# Power.net
KiCad netlist of a schematic drawn in EAGLE
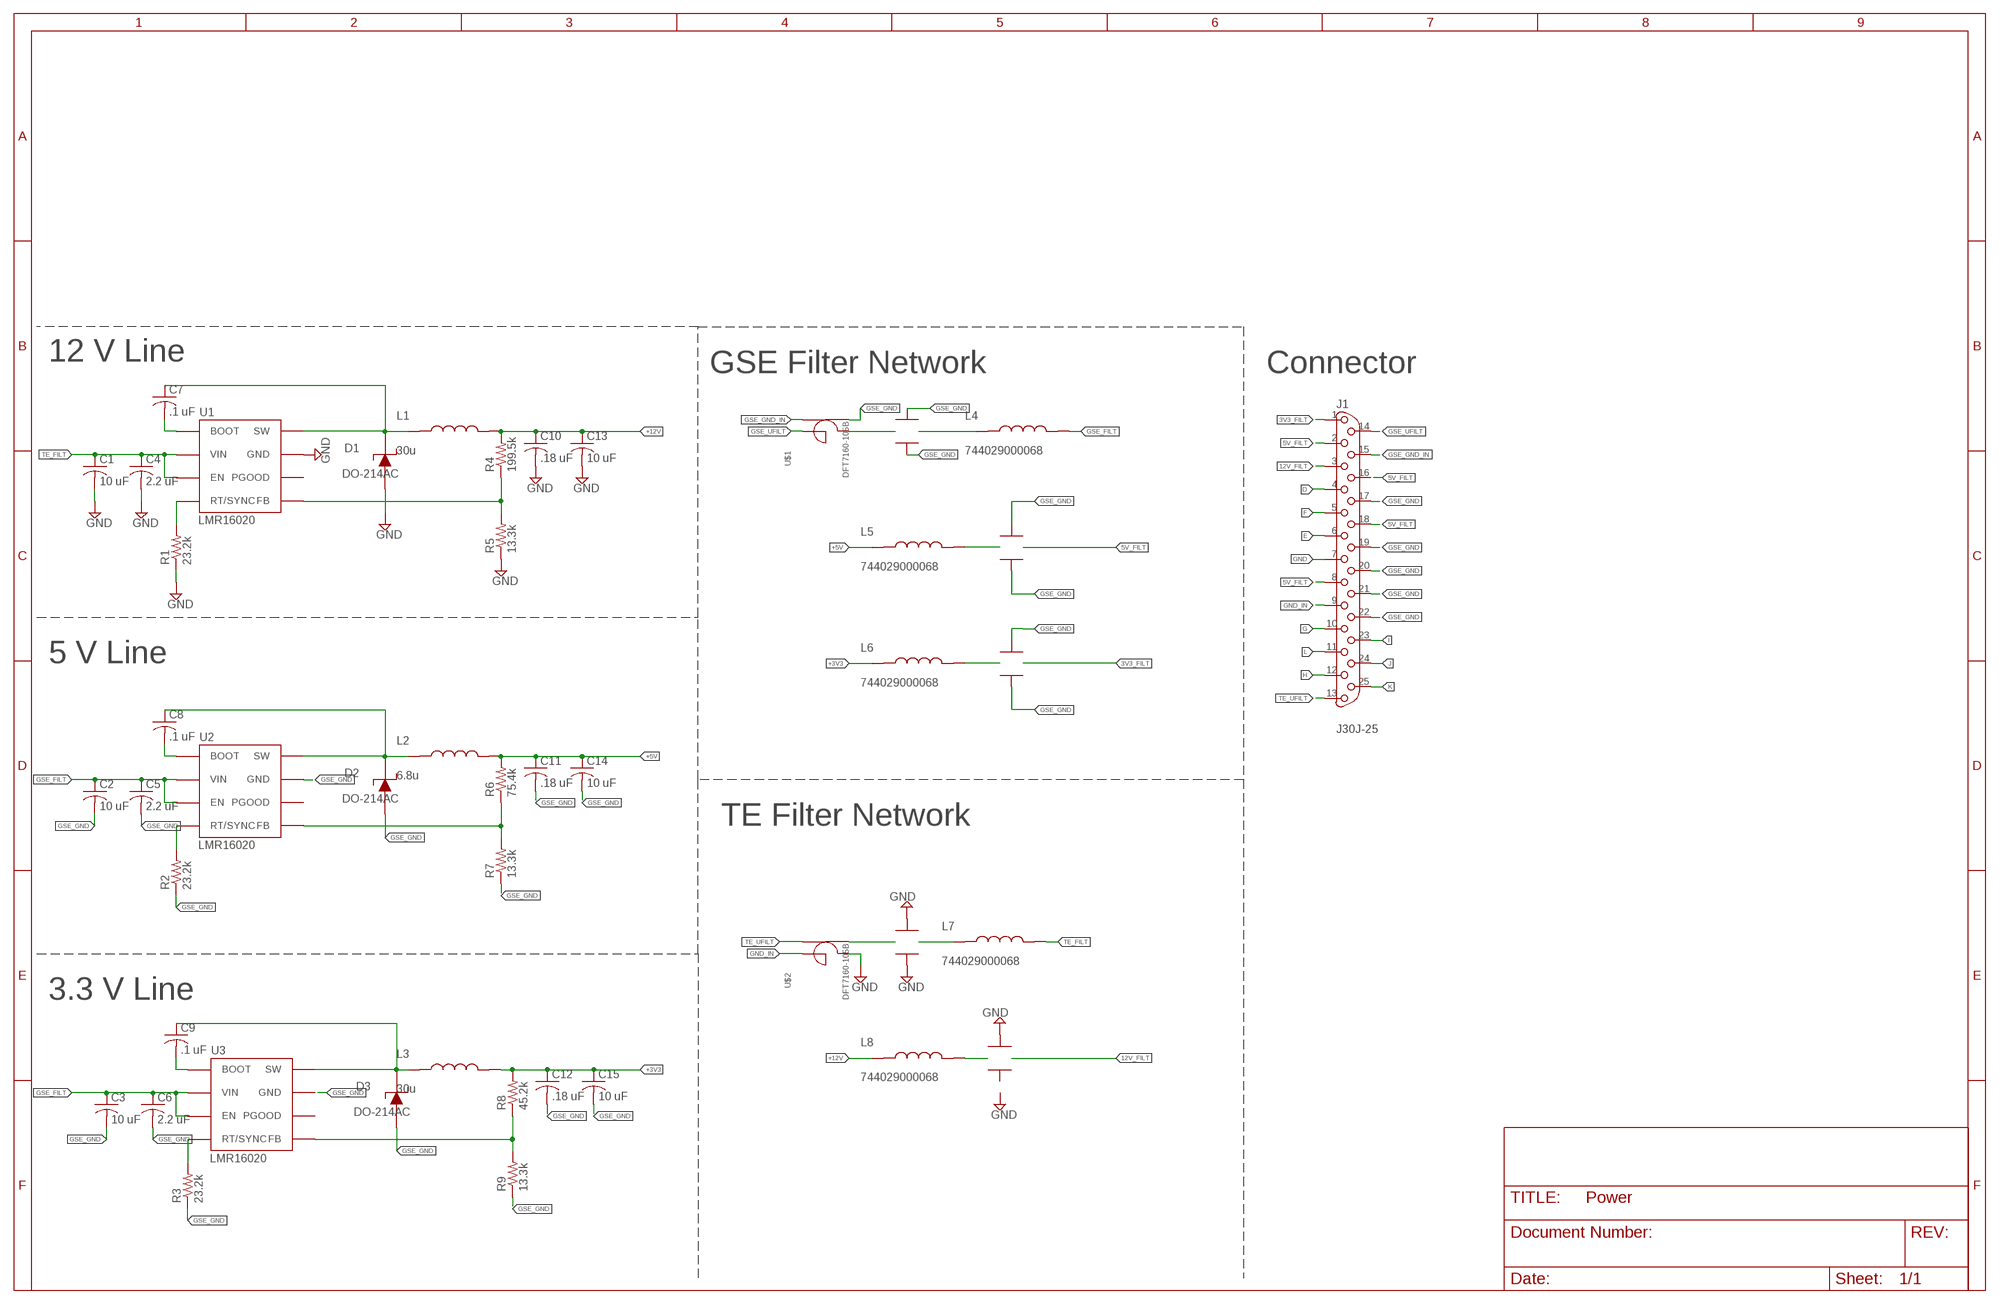
[diagram p0: schematic, sheet 1]

(export (version "E")
  (design (tool "Eeschema 10.0.6"))
  (components
    (comp (ref "C1")
      (value "10 uF")
      (footprint "eagle-import:C1210")
      (libsource (lib "eagle-import") (part "C-USC1210"))
    )
    (comp (ref "C2")
      (value "10 uF")
      (footprint "eagle-import:C1210")
      (libsource (lib "eagle-import") (part "C-USC1210"))
    )
    (comp (ref "C3")
      (value "10 uF")
      (footprint "eagle-import:C1210")
      (libsource (lib "eagle-import") (part "C-USC1210"))
    )
    (comp (ref "C4")
      (value "2.2 uF")
      (footprint "eagle-import:C1210")
      (libsource (lib "eagle-import") (part "C-USC1210"))
    )
    (comp (ref "C5")
      (value "2.2 uF")
      (footprint "eagle-import:C1210")
      (libsource (lib "eagle-import") (part "C-USC1210"))
    )
    (comp (ref "C6")
      (value "2.2 uF")
      (footprint "eagle-import:C1210")
      (libsource (lib "eagle-import") (part "C-USC1210"))
    )
    (comp (ref "C7")
      (value ".1 uF")
      (footprint "eagle-import:C0603")
      (libsource (lib "eagle-import") (part "C-USC0603"))
    )
    (comp (ref "C8")
      (value ".1 uF")
      (footprint "eagle-import:C0603")
      (libsource (lib "eagle-import") (part "C-USC0603"))
    )
    (comp (ref "C9")
      (value ".1 uF")
      (footprint "eagle-import:C0603")
      (libsource (lib "eagle-import") (part "C-USC0603"))
    )
    (comp (ref "C10")
      (value ".18 uF")
      (footprint "eagle-import:C0603")
      (libsource (lib "eagle-import") (part "C-USC0603"))
    )
    (comp (ref "C11")
      (value ".18 uF")
      (footprint "eagle-import:C0603")
      (libsource (lib "eagle-import") (part "C-USC0603"))
    )
    (comp (ref "C12")
      (value ".18 uF")
      (footprint "eagle-import:C0603")
      (libsource (lib "eagle-import") (part "C-USC0603"))
    )
    (comp (ref "C13")
      (value "10 uF")
      (footprint "eagle-import:C0603")
      (libsource (lib "eagle-import") (part "C-USC0603"))
    )
    (comp (ref "C14")
      (value "10 uF")
      (footprint "eagle-import:C0603")
      (libsource (lib "eagle-import") (part "C-USC0603"))
    )
    (comp (ref "C15")
      (value "10 uF")
      (footprint "eagle-import:C0603")
      (libsource (lib "eagle-import") (part "C-USC0603"))
    )
    (comp (ref "D1")
      (value "DO-214AC")
      (footprint "eagle-import:DO-214AC")
      (libsource (lib "eagle-import") (part "DO-214AC"))
    )
    (comp (ref "D2")
      (value "DO-214AC")
      (footprint "eagle-import:DO-214AC")
      (libsource (lib "eagle-import") (part "DO-214AC"))
    )
    (comp (ref "D3")
      (value "DO-214AC")
      (footprint "eagle-import:DO-214AC")
      (libsource (lib "eagle-import") (part "DO-214AC"))
    )
    (comp (ref "J1")
      (value "J30J-25")
      (footprint "eagle-import:ZKN-25")
      (libsource (lib "eagle-import") (part "J30J-25"))
    )
    (comp (ref "L1")
      (value "30u")
      (footprint "eagle-import:7050")
      (libsource (lib "eagle-import") (part "744314101"))
    )
    (comp (ref "L2")
      (value "6.8u")
      (footprint "eagle-import:7050")
      (libsource (lib "eagle-import") (part "744314101"))
    )
    (comp (ref "L3")
      (value "30u")
      (footprint "eagle-import:1365")
      (libsource (lib "eagle-import") (part "7443551370"))
    )
    (comp (ref "L4")
      (value "744029000068")
      (footprint "eagle-import:2813")
      (libsource (lib "eagle-import") (part "744029000068"))
    )
    (comp (ref "L5")
      (value "744029000068")
      (footprint "eagle-import:2813")
      (libsource (lib "eagle-import") (part "744029000068"))
    )
    (comp (ref "L6")
      (value "744029000068")
      (footprint "eagle-import:2813")
      (libsource (lib "eagle-import") (part "744029000068"))
    )
    (comp (ref "L7")
      (value "744029000068")
      (footprint "eagle-import:2813")
      (libsource (lib "eagle-import") (part "744029000068"))
    )
    (comp (ref "L8")
      (value "744029000068")
      (footprint "eagle-import:2813")
      (libsource (lib "eagle-import") (part "744029000068"))
    )
    (comp (ref "R1")
      (value "23.2k")
      (footprint "eagle-import:R0603")
      (libsource (lib "eagle-import") (part "R-US_R0603"))
    )
    (comp (ref "R2")
      (value "23.2k")
      (footprint "eagle-import:R0603")
      (libsource (lib "eagle-import") (part "R-US_R0603"))
    )
    (comp (ref "R3")
      (value "23.2k")
      (footprint "eagle-import:R0603")
      (libsource (lib "eagle-import") (part "R-US_R0603"))
    )
    (comp (ref "R4")
      (value "199.5k")
      (footprint "eagle-import:R0603")
      (libsource (lib "eagle-import") (part "R-US_R0603"))
    )
    (comp (ref "R5")
      (value "13.3k")
      (footprint "eagle-import:R0603")
      (libsource (lib "eagle-import") (part "R-US_R0603"))
    )
    (comp (ref "R6")
      (value "75.4k")
      (footprint "eagle-import:R0603")
      (libsource (lib "eagle-import") (part "R-US_R0603"))
    )
    (comp (ref "R7")
      (value "13.3k")
      (footprint "eagle-import:R0603")
      (libsource (lib "eagle-import") (part "R-US_R0603"))
    )
    (comp (ref "R8")
      (value "45.2k")
      (footprint "eagle-import:R0603")
      (libsource (lib "eagle-import") (part "R-US_R0603"))
    )
    (comp (ref "R9")
      (value "13.3k")
      (footprint "eagle-import:R0603")
      (libsource (lib "eagle-import") (part "R-US_R0603"))
    )
    (comp (ref "U$1")
      (value "DFT7160-105B")
      (footprint "eagle-import:DFT7160")
      (libsource (lib "eagle-import") (part "DFT7160-105B"))
    )
    (comp (ref "U$2")
      (value "DFT7160-105B")
      (footprint "eagle-import:DFT7160")
      (libsource (lib "eagle-import") (part "DFT7160-105B"))
    )
    (comp (ref "U$3")
      (value "1410J0500404MXTE03")
      (footprint "eagle-import:1410")
      (libsource (lib "eagle-import") (part "1410J0500404MXTE03"))
    )
    (comp (ref "U$4")
      (value "1410J0500404MXTE03")
      (footprint "eagle-import:1410")
      (libsource (lib "eagle-import") (part "1410J0500404MXTE03"))
    )
    (comp (ref "U$5")
      (value "1410J0500404MXTE03")
      (footprint "eagle-import:1410")
      (libsource (lib "eagle-import") (part "1410J0500404MXTE03"))
    )
    (comp (ref "U$6")
      (value "1410J0500404MXTE03")
      (footprint "eagle-import:1410")
      (libsource (lib "eagle-import") (part "1410J0500404MXTE03"))
    )
    (comp (ref "U$7")
      (value "1410J0500404MXTE03")
      (footprint "eagle-import:1410")
      (libsource (lib "eagle-import") (part "1410J0500404MXTE03"))
    )
    (comp (ref "U1")
      (value "LMR16020")
      (footprint "eagle-import:SO8")
      (libsource (lib "eagle-import") (part "LMR16020"))
    )
    (comp (ref "U2")
      (value "LMR16020")
      (footprint "eagle-import:SO8")
      (libsource (lib "eagle-import") (part "LMR16020"))
    )
    (comp (ref "U3")
      (value "LMR16020")
      (footprint "eagle-import:SO8")
      (libsource (lib "eagle-import") (part "LMR16020"))
    )
  )
  (nets
    (net (code "1") (name "+3V3") (class "Default")
      (node (ref "C12") (pin "1") (pinfunction "1_1") (pintype "passive"))
      (node (ref "C15") (pin "1") (pinfunction "1_1") (pintype "passive"))
      (node (ref "L3") (pin "P$2") (pinfunction "P$2_P$2") (pintype "bidirectional"))
      (node (ref "L6") (pin "P$1") (pinfunction "P$1_P$1") (pintype "bidirectional"))
      (node (ref "R8") (pin "2") (pinfunction "2_2") (pintype "passive"))
    )
    (net (code "2") (name "+5V") (class "Default")
      (node (ref "C11") (pin "1") (pinfunction "1_1") (pintype "passive"))
      (node (ref "C14") (pin "1") (pinfunction "1_1") (pintype "passive"))
      (node (ref "L2") (pin "P$2") (pinfunction "P$2_P$2") (pintype "bidirectional"))
      (node (ref "L5") (pin "P$1") (pinfunction "P$1_P$1") (pintype "bidirectional"))
      (node (ref "R6") (pin "2") (pinfunction "2_2") (pintype "passive"))
    )
    (net (code "3") (name "+12V") (class "Default")
      (node (ref "C10") (pin "1") (pinfunction "1_1") (pintype "passive"))
      (node (ref "C13") (pin "1") (pinfunction "1_1") (pintype "passive"))
      (node (ref "L1") (pin "P$2") (pinfunction "P$2_P$2") (pintype "bidirectional"))
      (node (ref "L8") (pin "P$1") (pinfunction "P$1_P$1") (pintype "bidirectional"))
      (node (ref "R4") (pin "2") (pinfunction "2_2") (pintype "passive"))
    )
    (net (code "4") (name "3V3_FILT") (class "Default")
      (node (ref "J1") (pin "1") (pinfunction "1_1") (pintype "bidirectional"))
      (node (ref "U$5") (pin "P$4") (pinfunction "P$3_P$4") (pintype "bidirectional"))
    )
    (net (code "5") (name "5V_FILT") (class "Default")
      (node (ref "J1") (pin "16") (pinfunction "16_16") (pintype "bidirectional"))
      (node (ref "J1") (pin "18") (pinfunction "18_18") (pintype "bidirectional"))
      (node (ref "J1") (pin "2") (pinfunction "2_2") (pintype "bidirectional"))
      (node (ref "J1") (pin "8") (pinfunction "8_8") (pintype "bidirectional"))
      (node (ref "U$4") (pin "P$4") (pinfunction "P$3_P$4") (pintype "bidirectional"))
    )
    (net (code "6") (name "12V_FILT") (class "Default")
      (node (ref "J1") (pin "3") (pinfunction "3_3") (pintype "bidirectional"))
      (node (ref "U$7") (pin "P$4") (pinfunction "P$3_P$4") (pintype "bidirectional"))
    )
    (net (code "7") (name "D") (class "Default")
      (node (ref "J1") (pin "4") (pinfunction "4_4") (pintype "bidirectional"))
    )
    (net (code "8") (name "E") (class "Default")
      (node (ref "J1") (pin "6") (pinfunction "6_6") (pintype "bidirectional"))
    )
    (net (code "9") (name "F") (class "Default")
      (node (ref "J1") (pin "5") (pinfunction "5_5") (pintype "bidirectional"))
    )
    (net (code "10") (name "G") (class "Default")
      (node (ref "J1") (pin "10") (pinfunction "10_10") (pintype "bidirectional"))
    )
    (net (code "11") (name "GND") (class "Default")
      (node (ref "C1") (pin "2") (pinfunction "2_2") (pintype "passive"))
      (node (ref "C10") (pin "2") (pinfunction "2_2") (pintype "passive"))
      (node (ref "C13") (pin "2") (pinfunction "2_2") (pintype "passive"))
      (node (ref "C4") (pin "2") (pinfunction "2_2") (pintype "passive"))
      (node (ref "D1") (pin "P$1") (pinfunction "P$1_P$1") (pintype "bidirectional"))
      (node (ref "J1") (pin "7") (pinfunction "7_7") (pintype "bidirectional"))
      (node (ref "R1") (pin "1") (pinfunction "1_1") (pintype "passive"))
      (node (ref "R5") (pin "1") (pinfunction "1_1") (pintype "passive"))
      (node (ref "U$2") (pin "P$4") (pinfunction "P$2_P$4") (pintype "bidirectional"))
      (node (ref "U$6") (pin "P$2") (pinfunction "P$1_P$2") (pintype "bidirectional"))
      (node (ref "U$6") (pin "P$3") (pinfunction "P$2_P$3") (pintype "bidirectional"))
      (node (ref "U$7") (pin "P$3") (pinfunction "P$2_P$3") (pintype "bidirectional"))
      (node (ref "U1") (pin "P$7") (pinfunction "GND_P$7") (pintype "bidirectional"))
      (node (ref "U1") (pin "PAD") (pinfunction "GND_PAD") (pintype "bidirectional"))
    )
    (net (code "12") (name "GND_IN") (class "Default")
      (node (ref "J1") (pin "9") (pinfunction "9_9") (pintype "bidirectional"))
      (node (ref "U$2") (pin "P$1") (pinfunction "P$1_P$1") (pintype "bidirectional"))
    )
    (net (code "13") (name "GSE_FILT") (class "Default")
      (node (ref "C2") (pin "1") (pinfunction "1_1") (pintype "passive"))
      (node (ref "C3") (pin "1") (pinfunction "1_1") (pintype "passive"))
      (node (ref "C5") (pin "1") (pinfunction "1_1") (pintype "passive"))
      (node (ref "C6") (pin "1") (pinfunction "1_1") (pintype "passive"))
      (node (ref "L4") (pin "P$2") (pinfunction "P$2_P$2") (pintype "bidirectional"))
      (node (ref "U2") (pin "P$2") (pinfunction "VIN_P$2") (pintype "bidirectional"))
      (node (ref "U2") (pin "P$3") (pinfunction "EN_P$3") (pintype "bidirectional"))
      (node (ref "U3") (pin "P$2") (pinfunction "VIN_P$2") (pintype "bidirectional"))
      (node (ref "U3") (pin "P$3") (pinfunction "EN_P$3") (pintype "bidirectional"))
    )
    (net (code "14") (name "GSE_GND") (class "Default")
      (node (ref "C11") (pin "2") (pinfunction "2_2") (pintype "passive"))
      (node (ref "C12") (pin "2") (pinfunction "2_2") (pintype "passive"))
      (node (ref "C14") (pin "2") (pinfunction "2_2") (pintype "passive"))
      (node (ref "C15") (pin "2") (pinfunction "2_2") (pintype "passive"))
      (node (ref "C2") (pin "2") (pinfunction "2_2") (pintype "passive"))
      (node (ref "C3") (pin "2") (pinfunction "2_2") (pintype "passive"))
      (node (ref "C5") (pin "2") (pinfunction "2_2") (pintype "passive"))
      (node (ref "C6") (pin "2") (pinfunction "2_2") (pintype "passive"))
      (node (ref "D2") (pin "P$1") (pinfunction "P$1_P$1") (pintype "bidirectional"))
      (node (ref "D3") (pin "P$1") (pinfunction "P$1_P$1") (pintype "bidirectional"))
      (node (ref "J1") (pin "17") (pinfunction "17_17") (pintype "bidirectional"))
      (node (ref "J1") (pin "19") (pinfunction "19_19") (pintype "bidirectional"))
      (node (ref "J1") (pin "20") (pinfunction "20_20") (pintype "bidirectional"))
      (node (ref "J1") (pin "21") (pinfunction "21_21") (pintype "bidirectional"))
      (node (ref "J1") (pin "22") (pinfunction "22_22") (pintype "bidirectional"))
      (node (ref "R2") (pin "1") (pinfunction "1_1") (pintype "passive"))
      (node (ref "R3") (pin "1") (pinfunction "1_1") (pintype "passive"))
      (node (ref "R7") (pin "1") (pinfunction "1_1") (pintype "passive"))
      (node (ref "R9") (pin "1") (pinfunction "1_1") (pintype "passive"))
      (node (ref "U$1") (pin "P$3") (pinfunction "P$4_P$3") (pintype "bidirectional"))
      (node (ref "U$3") (pin "P$2") (pinfunction "P$1_P$2") (pintype "bidirectional"))
      (node (ref "U$3") (pin "P$3") (pinfunction "P$2_P$3") (pintype "bidirectional"))
      (node (ref "U$4") (pin "P$2") (pinfunction "P$1_P$2") (pintype "bidirectional"))
      (node (ref "U$4") (pin "P$3") (pinfunction "P$2_P$3") (pintype "bidirectional"))
      (node (ref "U$5") (pin "P$2") (pinfunction "P$1_P$2") (pintype "bidirectional"))
      (node (ref "U$5") (pin "P$3") (pinfunction "P$2_P$3") (pintype "bidirectional"))
      (node (ref "U2") (pin "P$7") (pinfunction "GND_P$7") (pintype "bidirectional"))
      (node (ref "U2") (pin "PAD") (pinfunction "GND_PAD") (pintype "bidirectional"))
      (node (ref "U3") (pin "P$7") (pinfunction "GND_P$7") (pintype "bidirectional"))
      (node (ref "U3") (pin "PAD") (pinfunction "GND_PAD") (pintype "bidirectional"))
    )
    (net (code "15") (name "GSE_GND_IN") (class "Default")
      (node (ref "J1") (pin "15") (pinfunction "15_15") (pintype "bidirectional"))
      (node (ref "U$1") (pin "P$2") (pinfunction "P$3_P$2") (pintype "bidirectional"))
    )
    (net (code "16") (name "GSE_UFILT") (class "Default")
      (node (ref "J1") (pin "14") (pinfunction "14_14") (pintype "bidirectional"))
      (node (ref "U$1") (pin "P$1") (pinfunction "P$1_P$1") (pintype "bidirectional"))
    )
    (net (code "17") (name "H") (class "Default")
      (node (ref "J1") (pin "12") (pinfunction "12_12") (pintype "bidirectional"))
    )
    (net (code "18") (name "I") (class "Default")
      (node (ref "J1") (pin "23") (pinfunction "23_23") (pintype "bidirectional"))
    )
    (net (code "19") (name "J") (class "Default")
      (node (ref "J1") (pin "24") (pinfunction "24_24") (pintype "bidirectional"))
    )
    (net (code "20") (name "K") (class "Default")
      (node (ref "J1") (pin "25") (pinfunction "25_25") (pintype "bidirectional"))
    )
    (net (code "21") (name "L") (class "Default")
      (node (ref "J1") (pin "11") (pinfunction "11_11") (pintype "bidirectional"))
    )
    (net (code "22") (name "Net-(U$1-P$2)") (class "Default")
      (node (ref "U$1") (pin "P$4") (pinfunction "P$2_P$4") (pintype "bidirectional"))
      (node (ref "U$3") (pin "P$4") (pinfunction "P$3_P$4") (pintype "bidirectional"))
    )
    (net (code "23") (name "Net-(U$2-P$4)") (class "Default")
      (node (ref "U$2") (pin "P$3") (pinfunction "P$4_P$3") (pintype "bidirectional"))
      (node (ref "U$6") (pin "P$5") (pinfunction "P$4_P$5") (pintype "bidirectional"))
    )
    (net (code "24") (name "Net-(U$3-P$4)") (class "Default")
      (node (ref "L4") (pin "P$1") (pinfunction "P$1_P$1") (pintype "bidirectional"))
      (node (ref "U$3") (pin "P$5") (pinfunction "P$4_P$5") (pintype "bidirectional"))
    )
    (net (code "25") (name "Net-(U$4-P$4)") (class "Default")
      (node (ref "L5") (pin "P$2") (pinfunction "P$2_P$2") (pintype "bidirectional"))
      (node (ref "U$4") (pin "P$5") (pinfunction "P$4_P$5") (pintype "bidirectional"))
    )
    (net (code "26") (name "Net-(U$5-P$4)") (class "Default")
      (node (ref "L6") (pin "P$2") (pinfunction "P$2_P$2") (pintype "bidirectional"))
      (node (ref "U$5") (pin "P$5") (pinfunction "P$4_P$5") (pintype "bidirectional"))
    )
    (net (code "27") (name "Net-(U$6-P$3)") (class "Default")
      (node (ref "L7") (pin "P$1") (pinfunction "P$1_P$1") (pintype "bidirectional"))
      (node (ref "U$6") (pin "P$4") (pinfunction "P$3_P$4") (pintype "bidirectional"))
    )
    (net (code "28") (name "Net-(U$7-P$4)") (class "Default")
      (node (ref "L8") (pin "P$2") (pinfunction "P$2_P$2") (pintype "bidirectional"))
      (node (ref "U$7") (pin "P$5") (pinfunction "P$4_P$5") (pintype "bidirectional"))
    )
    (net (code "29") (name "Net-(U1-BOOT)") (class "Default")
      (node (ref "C7") (pin "2") (pinfunction "2_2") (pintype "passive"))
      (node (ref "U1") (pin "P$1") (pinfunction "BOOT_P$1") (pintype "bidirectional"))
    )
    (net (code "30") (name "Net-(U1-FB)") (class "Default")
      (node (ref "R4") (pin "1") (pinfunction "1_1") (pintype "passive"))
      (node (ref "R5") (pin "2") (pinfunction "2_2") (pintype "passive"))
      (node (ref "U1") (pin "P$5") (pinfunction "FB_P$5") (pintype "bidirectional"))
    )
    (net (code "31") (name "Net-(U1-RT{slash}SYNC)") (class "Default")
      (node (ref "R1") (pin "2") (pinfunction "2_2") (pintype "passive"))
      (node (ref "U1") (pin "P$4") (pinfunction "RT/SYNC_P$4") (pintype "bidirectional"))
    )
    (net (code "32") (name "Net-(U1-SW)") (class "Default")
      (node (ref "C7") (pin "1") (pinfunction "1_1") (pintype "passive"))
      (node (ref "D1") (pin "P$2") (pinfunction "P$2_P$2") (pintype "bidirectional"))
      (node (ref "L1") (pin "P$1") (pinfunction "P$1_P$1") (pintype "bidirectional"))
      (node (ref "U1") (pin "P$8") (pinfunction "SW_P$8") (pintype "bidirectional"))
    )
    (net (code "33") (name "Net-(U2-BOOT)") (class "Default")
      (node (ref "C8") (pin "2") (pinfunction "2_2") (pintype "passive"))
      (node (ref "U2") (pin "P$1") (pinfunction "BOOT_P$1") (pintype "bidirectional"))
    )
    (net (code "34") (name "Net-(U2-FB)") (class "Default")
      (node (ref "R6") (pin "1") (pinfunction "1_1") (pintype "passive"))
      (node (ref "R7") (pin "2") (pinfunction "2_2") (pintype "passive"))
      (node (ref "U2") (pin "P$5") (pinfunction "FB_P$5") (pintype "bidirectional"))
    )
    (net (code "35") (name "Net-(U2-RT{slash}SYNC)") (class "Default")
      (node (ref "R2") (pin "2") (pinfunction "2_2") (pintype "passive"))
      (node (ref "U2") (pin "P$4") (pinfunction "RT/SYNC_P$4") (pintype "bidirectional"))
    )
    (net (code "36") (name "Net-(U2-SW)") (class "Default")
      (node (ref "C8") (pin "1") (pinfunction "1_1") (pintype "passive"))
      (node (ref "D2") (pin "P$2") (pinfunction "P$2_P$2") (pintype "bidirectional"))
      (node (ref "L2") (pin "P$1") (pinfunction "P$1_P$1") (pintype "bidirectional"))
      (node (ref "U2") (pin "P$8") (pinfunction "SW_P$8") (pintype "bidirectional"))
    )
    (net (code "37") (name "Net-(U3-BOOT)") (class "Default")
      (node (ref "C9") (pin "2") (pinfunction "2_2") (pintype "passive"))
      (node (ref "U3") (pin "P$1") (pinfunction "BOOT_P$1") (pintype "bidirectional"))
    )
    (net (code "38") (name "Net-(U3-FB)") (class "Default")
      (node (ref "R8") (pin "1") (pinfunction "1_1") (pintype "passive"))
      (node (ref "R9") (pin "2") (pinfunction "2_2") (pintype "passive"))
      (node (ref "U3") (pin "P$5") (pinfunction "FB_P$5") (pintype "bidirectional"))
    )
    (net (code "39") (name "Net-(U3-RT{slash}SYNC)") (class "Default")
      (node (ref "R3") (pin "2") (pinfunction "2_2") (pintype "passive"))
      (node (ref "U3") (pin "P$4") (pinfunction "RT/SYNC_P$4") (pintype "bidirectional"))
    )
    (net (code "40") (name "Net-(U3-SW)") (class "Default")
      (node (ref "C9") (pin "1") (pinfunction "1_1") (pintype "passive"))
      (node (ref "D3") (pin "P$2") (pinfunction "P$2_P$2") (pintype "bidirectional"))
      (node (ref "L3") (pin "P$1") (pinfunction "P$1_P$1") (pintype "bidirectional"))
      (node (ref "U3") (pin "P$8") (pinfunction "SW_P$8") (pintype "bidirectional"))
    )
    (net (code "41") (name "TE_FILT") (class "Default")
      (node (ref "C1") (pin "1") (pinfunction "1_1") (pintype "passive"))
      (node (ref "C4") (pin "1") (pinfunction "1_1") (pintype "passive"))
      (node (ref "L7") (pin "P$2") (pinfunction "P$2_P$2") (pintype "bidirectional"))
      (node (ref "U1") (pin "P$2") (pinfunction "VIN_P$2") (pintype "bidirectional"))
      (node (ref "U1") (pin "P$3") (pinfunction "EN_P$3") (pintype "bidirectional"))
    )
    (net (code "42") (name "TE_UFILT") (class "Default")
      (node (ref "J1") (pin "13") (pinfunction "13_13") (pintype "bidirectional"))
      (node (ref "U$2") (pin "P$2") (pinfunction "P$3_P$2") (pintype "bidirectional"))
    )
    (net (code "43") (name "unconnected-(U$7-P$1-PadP$2)") (class "Default")
      (node (ref "U$7") (pin "P$2") (pinfunction "P$1_P$2") (pintype "bidirectional"))
    )
    (net (code "44") (name "unconnected-(U1-PGOOD-PadP$6)") (class "Default")
      (node (ref "U1") (pin "P$6") (pinfunction "PGOOD_P$6") (pintype "bidirectional"))
    )
    (net (code "45") (name "unconnected-(U2-PGOOD-PadP$6)") (class "Default")
      (node (ref "U2") (pin "P$6") (pinfunction "PGOOD_P$6") (pintype "bidirectional"))
    )
    (net (code "46") (name "unconnected-(U3-PGOOD-PadP$6)") (class "Default")
      (node (ref "U3") (pin "P$6") (pinfunction "PGOOD_P$6") (pintype "bidirectional"))
    )
  )
)
